# design.net
KiCad netlist of a schematic drawn in EasyEDA Pro
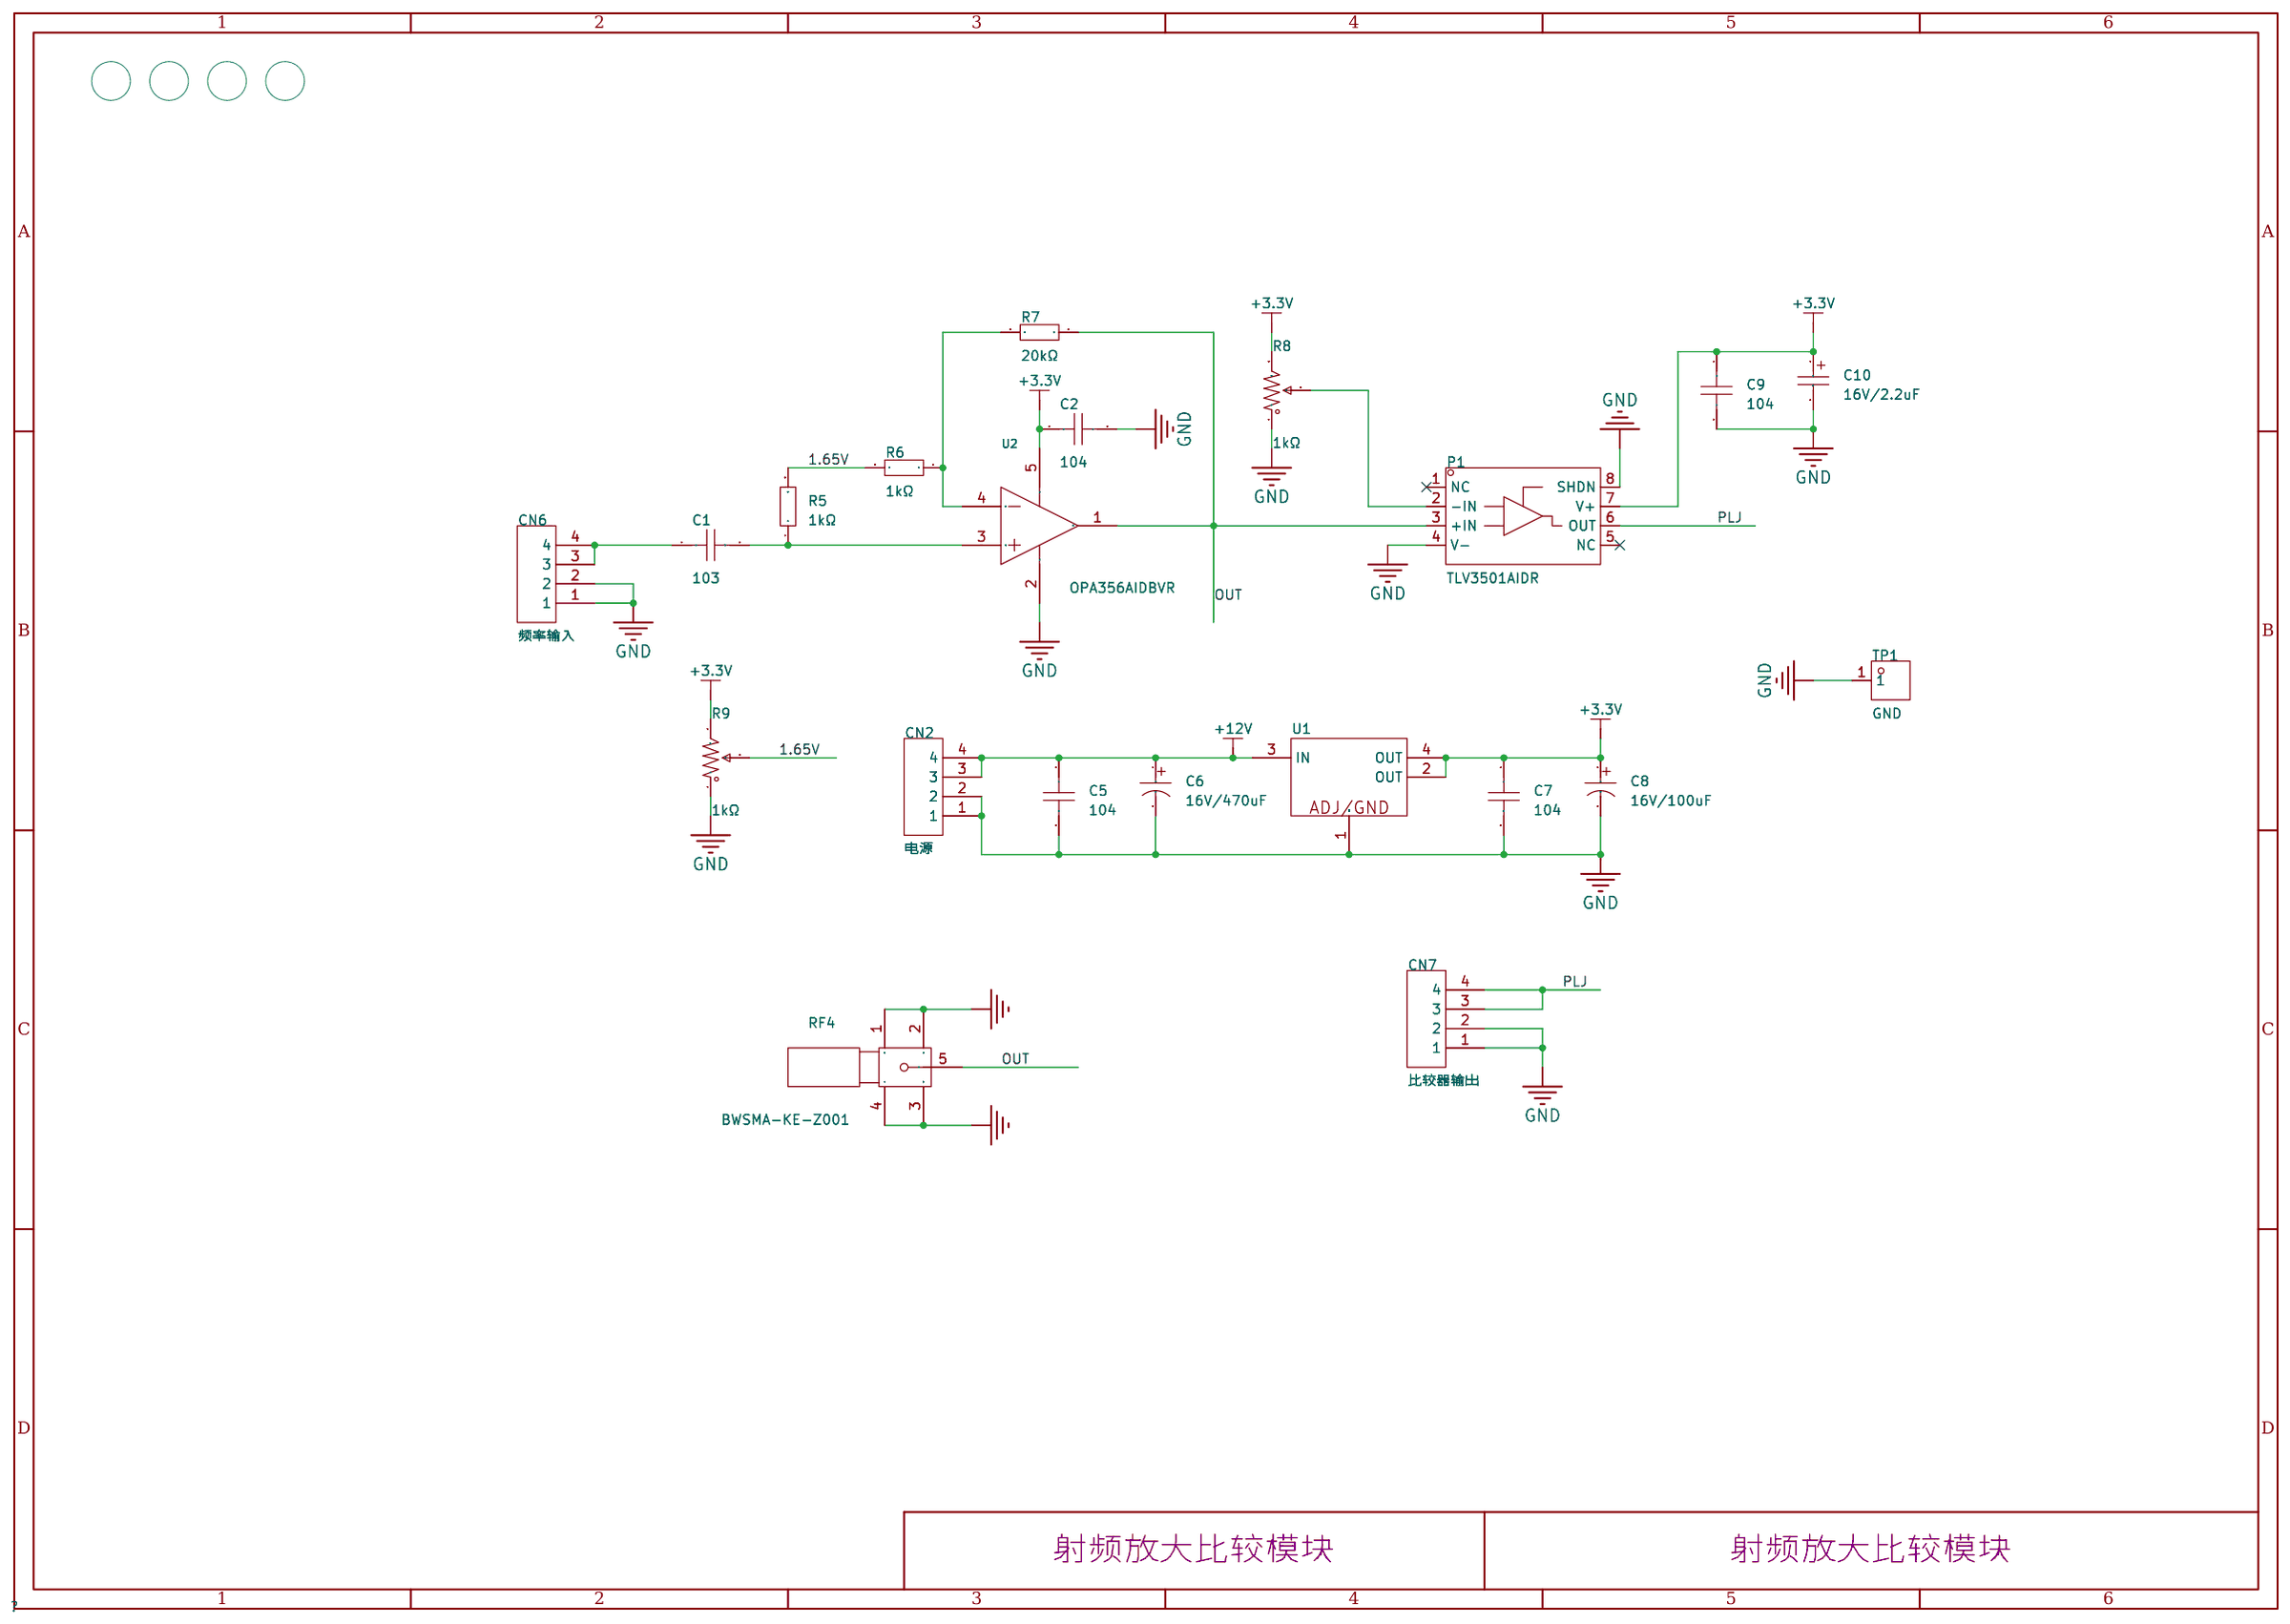
[diagram p0: schematic sheet]

(export (version "E")
  (design (tool "Eeschema 10.0.6"))
  (components
    (comp (ref "A1")
      (value "~")
      (footprint "easyedapro:POST_4mm")
      (libsource (lib "easyedapro") (part "安装孔"))
    )
    (comp (ref "A2")
      (value "~")
      (footprint "easyedapro:POST_4mm")
      (libsource (lib "easyedapro") (part "安装孔"))
    )
    (comp (ref "A3")
      (value "~")
      (footprint "easyedapro:POST_4mm")
      (libsource (lib "easyedapro") (part "安装孔"))
    )
    (comp (ref "A4")
      (value "~")
      (footprint "easyedapro:POST_4mm")
      (libsource (lib "easyedapro") (part "安装孔"))
    )
    (comp (ref "C1")
      (value "103")
      (footprint "easyedapro:CAP-TH_L7.2-W4.0-P5.00-D0.5")
      (description "容值:100nF;精度:±5%;额定电压:100V;工作温度:-40~+105;")
      (fields (field (name "Manufacturer Part") "MES104J2A-7-50R0") (field (name "Manufacturer") "HEL鸿志"))
      (libsource (lib "easyedapro") (part "MES104J2A-7-50R0"))
    )
    (comp (ref "C2")
      (value "104")
      (footprint "easyedapro:CAP-TH_L7.2-W4.0-P5.00-D0.5")
      (description "容值:100nF;精度:±5%;额定电压:100V;工作温度:-40~+105;")
      (fields (field (name "Manufacturer Part") "MES104J2A-7-50R0") (field (name "Manufacturer") "HEL鸿志"))
      (libsource (lib "easyedapro") (part "MES104J2A-7-50R0"))
    )
    (comp (ref "C5")
      (value "104")
      (footprint "easyedapro:CAP-TH_L7.2-W4.0-P5.00-D0.5")
      (description "容值:100nF;精度:±5%;额定电压:100V;工作温度:-40~+105;")
      (fields (field (name "Manufacturer Part") "MES104J2A-7-50R0") (field (name "Manufacturer") "HEL鸿志"))
      (libsource (lib "easyedapro") (part "MES104J2A-7-50R0"))
    )
    (comp (ref "C6")
      (value "16V/470uF")
      (footprint "easyedapro:CAP-TH_BD8.0-P3.50-D0.6-FD")
      (description "脚间距:3.5mm;电容体直径:8mm;精度:±20%;工作温度:-;额定电压:16V;容值:470uF;工作寿命:2000hrs 105°C;电容体长度:12mm;")
      (fields
        (field (name "Manufacturer Part") "KM477M016F12RR0VH2FP0")
        (field (name "Manufacturer") "CX(承兴)")
      )
      (libsource (lib "easyedapro") (part "16V/470uF"))
    )
    (comp (ref "C7")
      (value "104")
      (footprint "easyedapro:CAP-TH_L7.2-W4.0-P5.00-D0.5")
      (description "容值:100nF;精度:±5%;额定电压:100V;工作温度:-40~+105;")
      (fields (field (name "Manufacturer Part") "MES104J2A-7-50R0") (field (name "Manufacturer") "HEL鸿志"))
      (libsource (lib "easyedapro") (part "MES104J2A-7-50R0"))
    )
    (comp (ref "C8")
      (value "16V/100uF")
      (footprint "easyedapro:CAP-TH_BD6.3-P2.50-D1.0-FD")
      (fields
        (field (name "Manufacturer Part") "16ML100MEFC6.3X7")
        (field (name "Manufacturer") "rubycon(红宝石)")
      )
      (libsource (lib "easyedapro") (part "16V/100uF"))
    )
    (comp (ref "C9")
      (value "104")
      (footprint "easyedapro:CAP-TH_L7.2-W4.0-P5.00-D0.5")
      (description "容值:100nF;精度:±5%;额定电压:100V;工作温度:-40~+105;")
      (fields (field (name "Manufacturer Part") "MES104J2A-7-50R0") (field (name "Manufacturer") "HEL鸿志"))
      (libsource (lib "easyedapro") (part "MES104J2A-7-50R0"))
    )
    (comp (ref "C10")
      (value "16V/2.2uF")
      (footprint "easyedapro:CASE-A_3216")
      (description "容值:2.2uF;精度:±10%;额定电压:16V;等效串联电阻:6.5Ω@100kHz;")
      (fields (field (name "Manufacturer Part") "TAJA225K016RNJ") (field (name "Manufacturer") "Kyocera AVX"))
      (libsource (lib "easyedapro") (part "TAJA225K016RNJ"))
    )
    (comp (ref "CN2")
      (value "电源")
      (footprint "easyedapro:CONN-TH_4P-P2.54_A2510S-4P")
      (description "参考系列:-;间距:2.54mm;插针结构:1x4P;排数:1;每排PIN数:4;行距:-;安装方式:-;触头材质:黄铜;")
      (fields (field (name "Manufacturer Part") "W-2510S04P-0000") (field (name "Manufacturer") "Ckmtw(灿科盟)"))
      (libsource (lib "easyedapro") (part "2510S-4P"))
    )
    (comp (ref "CN6")
      (value "频率输入")
      (footprint "easyedapro:CONN-TH_4P-P2.54_A2510S-4P")
      (description "参考系列:-;间距:2.54mm;插针结构:1x4P;排数:1;每排PIN数:4;行距:-;安装方式:-;触头材质:黄铜;")
      (fields (field (name "Manufacturer Part") "W-2510S04P-0000") (field (name "Manufacturer") "Ckmtw(灿科盟)"))
      (libsource (lib "easyedapro") (part "2510S-4P"))
    )
    (comp (ref "CN7")
      (value "比较器输出")
      (footprint "easyedapro:CONN-TH_4P-P2.54_A2510S-4P")
      (description "参考系列:-;间距:2.54mm;插针结构:1x4P;排数:1;每排PIN数:4;行距:-;安装方式:-;触头材质:黄铜;")
      (fields (field (name "Manufacturer Part") "W-2510S04P-0000") (field (name "Manufacturer") "Ckmtw(灿科盟)"))
      (libsource (lib "easyedapro") (part "2510S-4P"))
    )
    (comp (ref "P1")
      (value "TLV3501AIDR")
      (footprint "easyedapro:SOP-8_L4.9-W3.9-P1.27-LS6.0-BL")
      (fields (field (name "Manufacturer") "TI(德州仪器)"))
      (libsource (lib "easyedapro") (part "TLV3501AIDR"))
    )
    (comp (ref "R5")
      (value "1kΩ")
      (footprint "easyedapro:RES-TH_BD2.5-L6.5-P10.50-D0.6")
      (description "电阻类型:金属膜电阻;阻值:1kΩ;精度:±1%;功率:250mW;温度系数:±50ppm/°C;")
      (fields
        (field (name "Manufacturer Part") "MFR0W4F1001A50")
        (field (name "Manufacturer") "UNI-ROYAL(厚声)")
      )
      (libsource (lib "easyedapro") (part "MFR0W4F1001A50"))
    )
    (comp (ref "R6")
      (value "1kΩ")
      (footprint "easyedapro:RES-TH_BD2.5-L6.5-P10.50-D0.6")
      (description "电阻类型:金属膜电阻;阻值:1kΩ;精度:±1%;功率:250mW;温度系数:±50ppm/°C;")
      (fields
        (field (name "Manufacturer Part") "MFR0W4F1001A50")
        (field (name "Manufacturer") "UNI-ROYAL(厚声)")
      )
      (libsource (lib "easyedapro") (part "MFR0W4F1001A50"))
    )
    (comp (ref "R7")
      (value "20kΩ")
      (footprint "easyedapro:RES-TH_BD2.5-L6.5-P10.50-D0.6")
      (description "电阻类型:金属膜电阻;阻值:1kΩ;精度:±1%;功率:250mW;温度系数:±50ppm/°C;")
      (fields
        (field (name "Manufacturer Part") "MFR0W4F1001A50")
        (field (name "Manufacturer") "UNI-ROYAL(厚声)")
      )
      (libsource (lib "easyedapro") (part "MFR0W4F1001A50"))
    )
    (comp (ref "R8")
      (value "1kΩ")
      (footprint "easyedapro:RES-ADJ-TH_3296P")
      (description "阻值:1kΩ;精度:±10%;功率:500mW;温度系数:-;")
      (fields (field (name "Manufacturer Part") "3296P-1-102LF") (field (name "Manufacturer") "BOURNS"))
      (libsource (lib "easyedapro") (part "3296P-1-102LF"))
    )
    (comp (ref "R9")
      (value "1kΩ")
      (footprint "easyedapro:RES-ADJ-TH_3296P")
      (description "阻值:1kΩ;精度:±10%;功率:500mW;温度系数:-;")
      (fields (field (name "Manufacturer Part") "3296P-1-102LF") (field (name "Manufacturer") "BOURNS"))
      (libsource (lib "easyedapro") (part "3296P-1-102LF"))
    )
    (comp (ref "RF4")
      (value "BWSMA-KE-Z001")
      (footprint "easyedapro:SMA-TH_BWSMA-KE-Z001")
      (fields (field (name "Manufacturer") "BAT WIRELESS(蝙蝠无线)"))
      (libsource (lib "easyedapro") (part "BWSMA-KE-Z001"))
    )
    (comp (ref "TP1")
      (value "GND")
      (footprint "easyedapro:TESTPOINT-TH_BD3.2")
      (fields (field (name "Manufacturer Part") "TP-黄色测试点"))
      (libsource (lib "easyedapro") (part "测试点"))
    )
    (comp (ref "U1")
      (value "AMS1117-3.3")
      (footprint "easyedapro:SOT-223-3_L6.4-W3.5-P2.30-LS7.0-BR")
      (fields (field (name "Manufacturer") "国芯佳品"))
      (libsource (lib "easyedapro") (part "AMS1117-3.3_C2992570"))
    )
    (comp (ref "U2")
      (value "OPA356AIDBVR")
      (footprint "easyedapro:SOT-23-5_L3.0-W1.7-P0.95-LS2.8-BR")
      (description "放大器组数:1;带宽(-3db):450MHz;输入偏置电流(Ib):3pA;增益带宽积(GBP):200MHz;压摆率(SR):360V/us;轨到轨:轨到轨;")
      (fields (field (name "Manufacturer") "TI(德州仪器)"))
      (libsource (lib "easyedapro") (part "OPA356AIDBVR"))
    )
  )
  (nets
    (net (code "1") (name "+3.3V") (class "Default")
      (node (ref "C10") (pin "1") (pinfunction "1_1") (pintype "input"))
      (node (ref "C2") (pin "1") (pinfunction "1_1") (pintype "input"))
      (node (ref "C7") (pin "1") (pinfunction "1_1") (pintype "input"))
      (node (ref "C8") (pin "1") (pinfunction "1_1") (pintype "input"))
      (node (ref "C9") (pin "1") (pinfunction "1_1") (pintype "input"))
      (node (ref "P1") (pin "7") (pinfunction "V+_7") (pintype "input"))
      (node (ref "R8") (pin "3") (pinfunction "3_3") (pintype "unspecified"))
      (node (ref "R9") (pin "3") (pinfunction "3_3") (pintype "unspecified"))
      (node (ref "U1") (pin "2") (pinfunction "OUT_2") (pintype "input"))
      (node (ref "U1") (pin "4") (pinfunction "OUT_4") (pintype "input"))
      (node (ref "U2") (pin "5") (pinfunction "V+_5") (pintype "input"))
    )
    (net (code "2") (name "+12V") (class "Default")
      (node (ref "C5") (pin "1") (pinfunction "1_1") (pintype "input"))
      (node (ref "C6") (pin "1") (pinfunction "1_1") (pintype "input"))
      (node (ref "CN2") (pin "3") (pinfunction "3_3") (pintype "input"))
      (node (ref "CN2") (pin "4") (pinfunction "4_4") (pintype "input"))
      (node (ref "U1") (pin "3") (pinfunction "IN_3") (pintype "input"))
    )
    (net (code "3") (name "/1.65V") (class "Default")
      (node (ref "R5") (pin "2") (pinfunction "2_2") (pintype "input"))
      (node (ref "R6") (pin "2") (pinfunction "2_2") (pintype "input"))
      (node (ref "R9") (pin "2") (pinfunction "2_2") (pintype "unspecified"))
    )
    (net (code "4") (name "/OUT") (class "Default")
      (node (ref "P1") (pin "3") (pinfunction "+IN_3") (pintype "input"))
      (node (ref "R7") (pin "1") (pinfunction "1_1") (pintype "input"))
      (node (ref "RF4") (pin "5") (pinfunction "5_5") (pintype "unspecified"))
      (node (ref "U2") (pin "1") (pinfunction "OUT_1") (pintype "output"))
    )
    (net (code "5") (name "/PLJ") (class "Default")
      (node (ref "CN7") (pin "3") (pinfunction "3_3") (pintype "input"))
      (node (ref "CN7") (pin "4") (pinfunction "4_4") (pintype "input"))
      (node (ref "P1") (pin "6") (pinfunction "OUT_6") (pintype "input"))
    )
    (net (code "6") (name "GND") (class "Default")
      (node (ref "C10") (pin "2") (pinfunction "2_2") (pintype "input"))
      (node (ref "C2") (pin "2") (pinfunction "2_2") (pintype "input"))
      (node (ref "C5") (pin "2") (pinfunction "2_2") (pintype "input"))
      (node (ref "C6") (pin "2") (pinfunction "2_2") (pintype "input"))
      (node (ref "C7") (pin "2") (pinfunction "2_2") (pintype "input"))
      (node (ref "C8") (pin "2") (pinfunction "2_2") (pintype "input"))
      (node (ref "C9") (pin "2") (pinfunction "2_2") (pintype "input"))
      (node (ref "CN2") (pin "1") (pinfunction "1_1") (pintype "input"))
      (node (ref "CN2") (pin "2") (pinfunction "2_2") (pintype "input"))
      (node (ref "CN6") (pin "1") (pinfunction "1_1") (pintype "input"))
      (node (ref "CN6") (pin "2") (pinfunction "2_2") (pintype "input"))
      (node (ref "CN7") (pin "1") (pinfunction "1_1") (pintype "input"))
      (node (ref "CN7") (pin "2") (pinfunction "2_2") (pintype "input"))
      (node (ref "P1") (pin "4") (pinfunction "V-_4") (pintype "input"))
      (node (ref "P1") (pin "8") (pinfunction "SHDN_8") (pintype "input"))
      (node (ref "R8") (pin "1") (pinfunction "1_1") (pintype "unspecified"))
      (node (ref "R9") (pin "1") (pinfunction "1_1") (pintype "unspecified"))
      (node (ref "RF4") (pin "1") (pinfunction "1_1") (pintype "unspecified"))
      (node (ref "RF4") (pin "2") (pinfunction "2_2") (pintype "unspecified"))
      (node (ref "RF4") (pin "3") (pinfunction "3_3") (pintype "unspecified"))
      (node (ref "RF4") (pin "4") (pinfunction "4_4") (pintype "unspecified"))
      (node (ref "TP1") (pin "1") (pinfunction "1_1") (pintype "input"))
      (node (ref "U1") (pin "1") (pinfunction "ADJ/GND_1") (pintype "input"))
      (node (ref "U2") (pin "2") (pinfunction "V-_2") (pintype "input"))
    )
    (net (code "7") (name "Net-(C1-Pad1)") (class "Default")
      (node (ref "C1") (pin "1") (pinfunction "1_1") (pintype "input"))
      (node (ref "CN6") (pin "3") (pinfunction "3_3") (pintype "input"))
      (node (ref "CN6") (pin "4") (pinfunction "4_4") (pintype "input"))
    )
    (net (code "8") (name "Net-(P1--IN)") (class "Default")
      (node (ref "P1") (pin "2") (pinfunction "-IN_2") (pintype "input"))
      (node (ref "R8") (pin "2") (pinfunction "2_2") (pintype "unspecified"))
    )
    (net (code "9") (name "Net-(U2-IN+)") (class "Default")
      (node (ref "C1") (pin "2") (pinfunction "2_2") (pintype "input"))
      (node (ref "R5") (pin "1") (pinfunction "1_1") (pintype "input"))
      (node (ref "U2") (pin "3") (pinfunction "IN+_3") (pintype "input"))
    )
    (net (code "10") (name "Net-(U2-IN-)") (class "Default")
      (node (ref "R6") (pin "1") (pinfunction "1_1") (pintype "input"))
      (node (ref "R7") (pin "2") (pinfunction "2_2") (pintype "input"))
      (node (ref "U2") (pin "4") (pinfunction "IN-_4") (pintype "input"))
    )
    (net (code "11") (name "unconnected-(P1-NC-Pad1)") (class "Default")
      (node (ref "P1") (pin "1") (pinfunction "NC_1") (pintype "input+no_connect"))
    )
    (net (code "12") (name "unconnected-(P1-NC-Pad5)") (class "Default")
      (node (ref "P1") (pin "5") (pinfunction "NC_5") (pintype "input+no_connect"))
    )
  )
)
